# C.net
KiCad netlist of a schematic drawn in Altium Designer
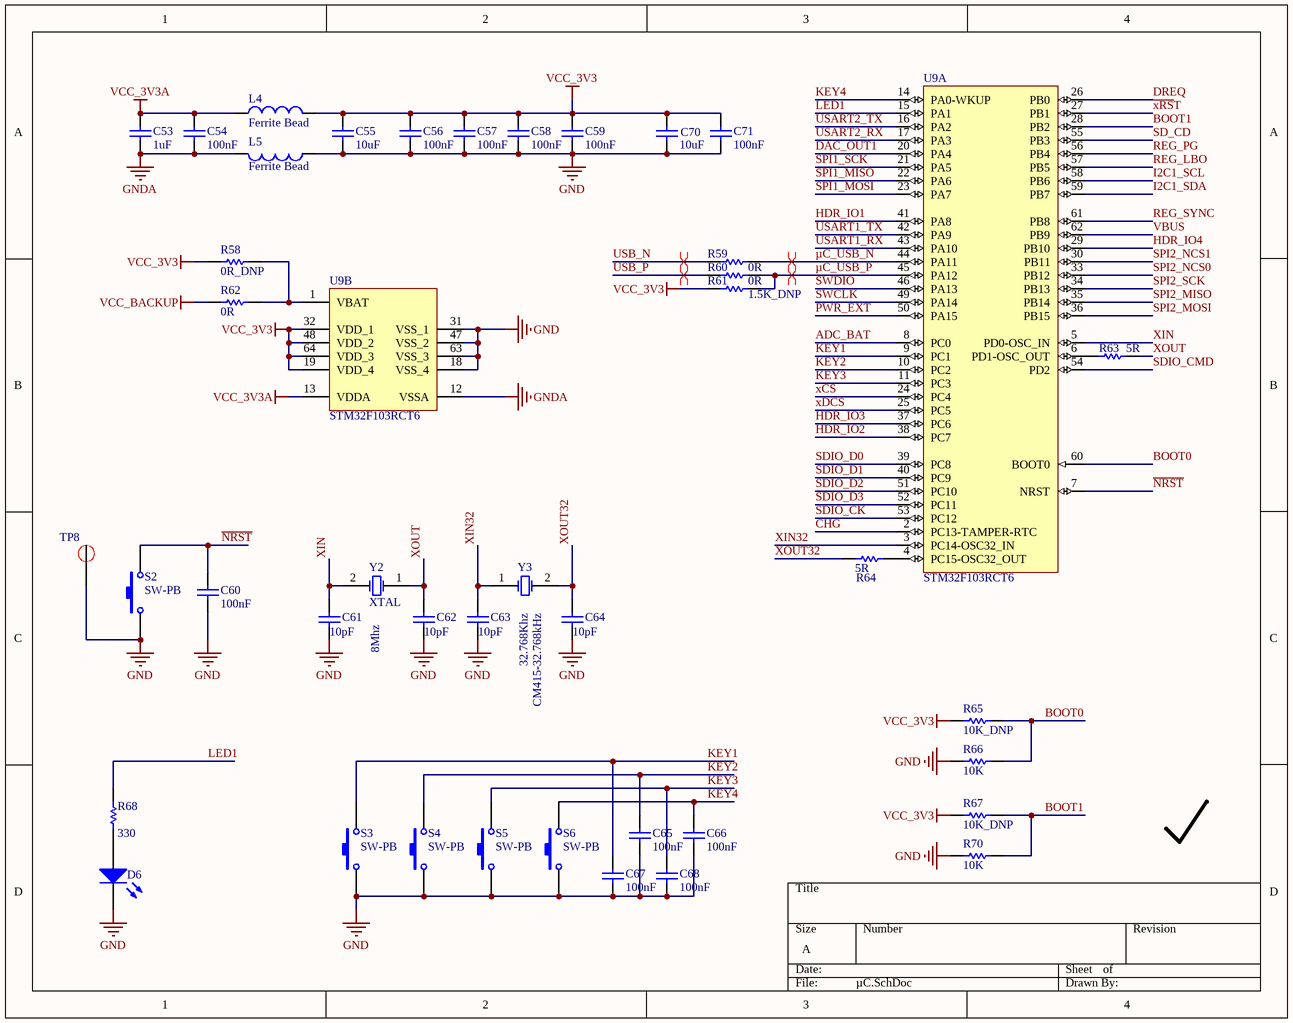
[diagram p0: µC.SchDoc]

(export (version "E")
  (design (tool "Eeschema 10.0.6"))
  (components
    (comp (ref "C53")
      (value "1uF")
      (footprint "0603PKG")
      (description "Capacitor (Semiconductor SIM Model)")
      (fields (field (name "Comment") "Cap Semi") (field (name "PUBLISHER") "Altium Limited"))
      (libsource (lib "Miscellaneous Devices") (part "Cap Semi"))
    )
    (comp (ref "C54")
      (value "100nF")
      (footprint "0603PKG")
      (description "Capacitor (Semiconductor SIM Model)")
      (fields (field (name "Comment") "Cap Semi") (field (name "PUBLISHER") "Altium Limited"))
      (libsource (lib "Miscellaneous Devices") (part "Cap Semi"))
    )
    (comp (ref "C55")
      (value "10uF")
      (footprint "0603PKG")
      (description "Capacitor (Semiconductor SIM Model)")
      (fields (field (name "Comment") "Cap Semi") (field (name "PUBLISHER") "Altium Limited"))
      (libsource (lib "Miscellaneous Devices") (part "Cap Semi"))
    )
    (comp (ref "C56")
      (value "100nF")
      (footprint "0603PKG")
      (description "Capacitor (Semiconductor SIM Model)")
      (fields (field (name "Comment") "Cap Semi") (field (name "PUBLISHER") "Altium Limited"))
      (libsource (lib "Miscellaneous Devices") (part "Cap Semi"))
    )
    (comp (ref "C57")
      (value "100nF")
      (footprint "0603PKG")
      (description "Capacitor (Semiconductor SIM Model)")
      (fields (field (name "Comment") "Cap Semi") (field (name "PUBLISHER") "Altium Limited"))
      (libsource (lib "Miscellaneous Devices") (part "Cap Semi"))
    )
    (comp (ref "C58")
      (value "100nF")
      (footprint "0603PKG")
      (description "Capacitor (Semiconductor SIM Model)")
      (fields (field (name "Comment") "Cap Semi") (field (name "PUBLISHER") "Altium Limited"))
      (libsource (lib "Miscellaneous Devices") (part "Cap Semi"))
    )
    (comp (ref "C59")
      (value "100nF")
      (footprint "0603PKG")
      (description "Capacitor (Semiconductor SIM Model)")
      (fields (field (name "Comment") "Cap Semi") (field (name "PUBLISHER") "Altium Limited"))
      (libsource (lib "Miscellaneous Devices") (part "Cap Semi"))
    )
    (comp (ref "C60")
      (value "100nF")
      (footprint "0603PKG")
      (description "Capacitor (Semiconductor SIM Model)")
      (fields (field (name "Comment") "Cap Semi") (field (name "PUBLISHER") "Altium Limited"))
      (libsource (lib "Miscellaneous Devices") (part "Cap Semi"))
    )
    (comp (ref "C61")
      (value "10pF")
      (footprint "0603PKG")
      (description "Capacitor")
      (fields (field (name "Comment") "Cap") (field (name "PUBLISHER") "Altium Limited"))
      (libsource (lib "Miscellaneous Devices") (part "Cap"))
    )
    (comp (ref "C62")
      (value "10pF")
      (footprint "0603PKG")
      (description "Capacitor")
      (fields (field (name "Comment") "Cap") (field (name "PUBLISHER") "Altium Limited"))
      (libsource (lib "Miscellaneous Devices") (part "Cap"))
    )
    (comp (ref "C63")
      (value "10pF")
      (footprint "0603PKG")
      (description "Capacitor")
      (fields (field (name "Comment") "Cap") (field (name "PUBLISHER") "Altium Limited"))
      (libsource (lib "Miscellaneous Devices") (part "Cap"))
    )
    (comp (ref "C64")
      (value "10pF")
      (footprint "0603PKG")
      (description "Capacitor")
      (fields (field (name "Comment") "Cap") (field (name "PUBLISHER") "Altium Limited"))
      (libsource (lib "Miscellaneous Devices") (part "Cap"))
    )
    (comp (ref "C65")
      (value "100nF")
      (footprint "0603PKG")
      (description "Capacitor (Semiconductor SIM Model)")
      (fields (field (name "Comment") "Cap Semi") (field (name "PUBLISHER") "Altium Limited"))
      (libsource (lib "Miscellaneous Devices") (part "Cap Semi"))
    )
    (comp (ref "C66")
      (value "100nF")
      (footprint "0603PKG")
      (description "Capacitor (Semiconductor SIM Model)")
      (fields (field (name "Comment") "Cap Semi") (field (name "PUBLISHER") "Altium Limited"))
      (libsource (lib "Miscellaneous Devices") (part "Cap Semi"))
    )
    (comp (ref "C67")
      (value "100nF")
      (footprint "0603PKG")
      (description "Capacitor (Semiconductor SIM Model)")
      (fields (field (name "Comment") "Cap Semi") (field (name "PUBLISHER") "Altium Limited"))
      (libsource (lib "Miscellaneous Devices") (part "Cap Semi"))
    )
    (comp (ref "C68")
      (value "100nF")
      (footprint "0603PKG")
      (description "Capacitor (Semiconductor SIM Model)")
      (fields (field (name "Comment") "Cap Semi") (field (name "PUBLISHER") "Altium Limited"))
      (libsource (lib "Miscellaneous Devices") (part "Cap Semi"))
    )
    (comp (ref "C70")
      (value "10uF")
      (footprint "C0805")
      (description "Capacitor (Semiconductor SIM Model)")
      (fields (field (name "Comment") "Cap Semi") (field (name "PUBLISHER") "Altium Limited"))
      (libsource (lib "Miscellaneous Devices") (part "Cap Semi"))
    )
    (comp (ref "C71")
      (value "100nF")
      (footprint "C0805")
      (description "Capacitor (Semiconductor SIM Model)")
      (fields (field (name "Comment") "Cap Semi") (field (name "PUBLISHER") "Altium Limited"))
      (libsource (lib "Miscellaneous Devices") (part "Cap Semi"))
    )
    (comp (ref "D6")
      (value "LED0")
      (footprint "C0805")
      (description "Typical INFRARED GaAs LED")
      (fields (field (name "PUBLISHER") "Altium Limited"))
      (libsource (lib "Miscellaneous Devices") (part "LED0"))
    )
    (comp (ref "L4")
      (value "Ferrite Bead")
      (footprint "C0805")
      (description "Inductor")
      (fields (field (name "PUBLISHER") "Altium Limited"))
      (libsource (lib "Miscellaneous Devices") (part "Inductor"))
    )
    (comp (ref "L5")
      (value "Ferrite Bead")
      (footprint "C0805")
      (description "Inductor")
      (fields (field (name "PUBLISHER") "Altium Limited"))
      (libsource (lib "Miscellaneous Devices") (part "Inductor"))
    )
    (comp (ref "R58")
      (value "0R_DNP")
      (footprint "0603PKG")
      (description "Resistor")
      (fields (field (name "Comment") "Res1") (field (name "PUBLISHER") "Altium Limited"))
      (libsource (lib "Miscellaneous Devices") (part "Res1"))
    )
    (comp (ref "R59")
      (value "0R")
      (footprint "0603PKG")
      (description "Resistor")
      (fields (field (name "Comment") "Res1") (field (name "PUBLISHER") "Altium Limited"))
      (libsource (lib "Miscellaneous Devices") (part "Res1"))
    )
    (comp (ref "R60")
      (value "0R")
      (footprint "0603PKG")
      (description "Resistor")
      (fields (field (name "Comment") "Res1") (field (name "PUBLISHER") "Altium Limited"))
      (libsource (lib "Miscellaneous Devices") (part "Res1"))
    )
    (comp (ref "R61")
      (value "1.5K_DNP")
      (footprint "0603PKG")
      (description "Resistor")
      (fields (field (name "Comment") "Res1") (field (name "PUBLISHER") "Altium Limited"))
      (libsource (lib "Miscellaneous Devices") (part "Res1"))
    )
    (comp (ref "R62")
      (value "0R")
      (footprint "0603PKG")
      (description "Resistor")
      (fields (field (name "Comment") "Res1") (field (name "PUBLISHER") "Altium Limited"))
      (libsource (lib "Miscellaneous Devices") (part "Res1"))
    )
    (comp (ref "R63")
      (value "5R")
      (footprint "0603PKG")
      (description "Resistor")
      (fields (field (name "Comment") "Res1") (field (name "PUBLISHER") "Altium Limited"))
      (libsource (lib "Miscellaneous Devices") (part "Res1"))
    )
    (comp (ref "R64")
      (value "5R")
      (footprint "0603PKG")
      (description "Resistor")
      (fields (field (name "Comment") "Res1") (field (name "PUBLISHER") "Altium Limited"))
      (libsource (lib "Miscellaneous Devices") (part "Res1"))
    )
    (comp (ref "R65")
      (value "10K_DNP")
      (footprint "0603PKG")
      (description "Resistor")
      (fields (field (name "Comment") "Res1") (field (name "PUBLISHER") "Altium Limited"))
      (libsource (lib "Miscellaneous Devices") (part "Res1"))
    )
    (comp (ref "R66")
      (value "10K")
      (footprint "0603PKG")
      (description "Resistor")
      (fields (field (name "Comment") "Res1") (field (name "PUBLISHER") "Altium Limited"))
      (libsource (lib "Miscellaneous Devices") (part "Res1"))
    )
    (comp (ref "R67")
      (value "10K_DNP")
      (footprint "0603PKG")
      (description "Resistor")
      (fields (field (name "Comment") "Res1") (field (name "PUBLISHER") "Altium Limited"))
      (libsource (lib "Miscellaneous Devices") (part "Res1"))
    )
    (comp (ref "R68")
      (value "330")
      (footprint "0603PKG")
      (description "Semiconductor Resistor")
      (fields (field (name "Comment") "Res Semi") (field (name "PUBLISHER") "Altium Limited"))
      (libsource (lib "Miscellaneous Devices") (part "Res Semi"))
    )
    (comp (ref "R70")
      (value "10K")
      (footprint "0603PKG")
      (description "Resistor")
      (fields (field (name "Comment") "Res1") (field (name "PUBLISHER") "Altium Limited"))
      (libsource (lib "Miscellaneous Devices") (part "Res1"))
    )
    (comp (ref "S2")
      (value "SW-PB")
      (footprint "SMD push button")
      (description "Switch")
      (fields (field (name "PUBLISHER") "Altium Limited"))
      (libsource (lib "Miscellaneous Devices") (part "SW-PB"))
    )
    (comp (ref "S3")
      (value "SW-PB")
      (footprint "SMD push button")
      (description "Switch")
      (fields (field (name "PUBLISHER") "Altium Limited"))
      (libsource (lib "Miscellaneous Devices") (part "SW-PB"))
    )
    (comp (ref "S4")
      (value "SW-PB")
      (footprint "SMD push button")
      (description "Switch")
      (fields (field (name "PUBLISHER") "Altium Limited"))
      (libsource (lib "Miscellaneous Devices") (part "SW-PB"))
    )
    (comp (ref "S5")
      (value "SW-PB")
      (footprint "SMD push button")
      (description "Switch")
      (fields (field (name "PUBLISHER") "Altium Limited"))
      (libsource (lib "Miscellaneous Devices") (part "SW-PB"))
    )
    (comp (ref "S6")
      (value "SW-PB")
      (footprint "SMD push button")
      (description "Switch")
      (fields (field (name "PUBLISHER") "Altium Limited"))
      (libsource (lib "Miscellaneous Devices") (part "SW-PB"))
    )
    (comp (ref "TP8")
      (value "TP")
      (footprint "TP_15")
      (libsource (lib "Connector_IntLib") (part "Test Point"))
    )
    (comp (ref "U9")
      (value "STM32F103RCT6")
      (footprint "LQFP64")
      (libsource (lib "STMicroelectronics STM32 F1") (part "STM32F103RCT6"))
    )
    (comp (ref "Y2")
      (value "XTAL")
      (footprint "SMD_Crystal")
      (description "Crystal Oscillator")
      (fields (field (name "ALTIUM_VALUE") "8Mhz") (field (name "PUBLISHER") "Altium Limited"))
      (libsource (lib "Miscellaneous Devices") (part "XTAL"))
    )
    (comp (ref "Y3")
      (value "CM415-32.768kHz")
      (footprint "CM415")
      (description "Crystal Oscillator CM415-32.768kHz")
      (fields (field (name "ALTIUM_VALUE") "32.768Khz") (field (name "PUBLISHER") "Altium Limited"))
      (libsource (lib "Miscellaneous Devices") (part "XTAL"))
    )
  )
  (nets
    (net (code "1") (name "/ADC_BAT") (class "Default")
      (node (ref "U9") (pin "8") (pinfunction "PC0_8") (pintype "bidirectional"))
    )
    (net (code "2") (name "/BOOT0") (class "Default")
      (node (ref "R65") (pin "1") (pinfunction "1_1") (pintype "passive"))
      (node (ref "R66") (pin "1") (pinfunction "1_1") (pintype "passive"))
      (node (ref "U9") (pin "60") (pinfunction "BOOT0_60") (pintype "input"))
    )
    (net (code "3") (name "/BOOT1") (class "Default")
      (node (ref "R67") (pin "1") (pinfunction "1_1") (pintype "passive"))
      (node (ref "R70") (pin "1") (pinfunction "1_1") (pintype "passive"))
      (node (ref "U9") (pin "28") (pinfunction "PB2_28") (pintype "bidirectional"))
    )
    (net (code "4") (name "/DAC_OUT1") (class "Default")
      (node (ref "U9") (pin "20") (pinfunction "PA4_20") (pintype "bidirectional"))
    )
    (net (code "5") (name "/DREQ") (class "Default")
      (node (ref "U9") (pin "26") (pinfunction "PB0_26") (pintype "bidirectional"))
    )
    (net (code "6") (name "/HDR_IO1") (class "Default")
      (node (ref "U9") (pin "41") (pinfunction "PA8_41") (pintype "bidirectional"))
    )
    (net (code "7") (name "/HDR_IO2") (class "Default")
      (node (ref "U9") (pin "38") (pinfunction "PC7_38") (pintype "bidirectional"))
    )
    (net (code "8") (name "/HDR_IO3") (class "Default")
      (node (ref "U9") (pin "37") (pinfunction "PC6_37") (pintype "bidirectional"))
    )
    (net (code "9") (name "/HDR_IO4") (class "Default")
      (node (ref "U9") (pin "29") (pinfunction "PB10_29") (pintype "bidirectional"))
    )
    (net (code "10") (name "/I2C1_SCL") (class "Default")
      (node (ref "U9") (pin "58") (pinfunction "PB6_58") (pintype "bidirectional"))
    )
    (net (code "11") (name "/I2C1_SDA") (class "Default")
      (node (ref "U9") (pin "59") (pinfunction "PB7_59") (pintype "bidirectional"))
    )
    (net (code "12") (name "/KEY1") (class "Default")
      (node (ref "C67") (pin "2") (pinfunction "2_2") (pintype "passive"))
      (node (ref "S3") (pin "2") (pinfunction "2_2") (pintype "passive"))
      (node (ref "U9") (pin "9") (pinfunction "PC1_9") (pintype "bidirectional"))
    )
    (net (code "13") (name "/KEY2") (class "Default")
      (node (ref "C65") (pin "2") (pinfunction "2_2") (pintype "passive"))
      (node (ref "S4") (pin "2") (pinfunction "2_2") (pintype "passive"))
      (node (ref "U9") (pin "10") (pinfunction "PC2_10") (pintype "bidirectional"))
    )
    (net (code "14") (name "/KEY3") (class "Default")
      (node (ref "C68") (pin "2") (pinfunction "2_2") (pintype "passive"))
      (node (ref "S5") (pin "2") (pinfunction "2_2") (pintype "passive"))
      (node (ref "U9") (pin "11") (pinfunction "PC3_11") (pintype "bidirectional"))
    )
    (net (code "15") (name "/KEY4") (class "Default")
      (node (ref "C66") (pin "2") (pinfunction "2_2") (pintype "passive"))
      (node (ref "S6") (pin "2") (pinfunction "2_2") (pintype "passive"))
      (node (ref "U9") (pin "14") (pinfunction "PA0-WKUP_14") (pintype "bidirectional"))
    )
    (net (code "16") (name "/LED1") (class "Default")
      (node (ref "R68") (pin "2") (pinfunction "2_2") (pintype "passive"))
      (node (ref "U9") (pin "15") (pinfunction "PA1_15") (pintype "bidirectional"))
    )
    (net (code "17") (name "/PWR_EXT") (class "Default")
      (node (ref "U9") (pin "50") (pinfunction "PA15_50") (pintype "bidirectional"))
    )
    (net (code "18") (name "/REG_LBO") (class "Default")
      (node (ref "U9") (pin "57") (pinfunction "PB5_57") (pintype "bidirectional"))
    )
    (net (code "19") (name "/REG_PG") (class "Default")
      (node (ref "U9") (pin "56") (pinfunction "PB4_56") (pintype "bidirectional"))
    )
    (net (code "20") (name "/REG_SYNC") (class "Default")
      (node (ref "U9") (pin "61") (pinfunction "PB8_61") (pintype "bidirectional"))
    )
    (net (code "21") (name "/SDIO_CK") (class "Default")
      (node (ref "U9") (pin "53") (pinfunction "PC12_53") (pintype "bidirectional"))
    )
    (net (code "22") (name "/SDIO_CMD") (class "Default")
      (node (ref "U9") (pin "54") (pinfunction "PD2_54") (pintype "bidirectional"))
    )
    (net (code "23") (name "/SDIO_D0") (class "Default")
      (node (ref "U9") (pin "39") (pinfunction "PC8_39") (pintype "bidirectional"))
    )
    (net (code "24") (name "/SDIO_D1") (class "Default")
      (node (ref "U9") (pin "40") (pinfunction "PC9_40") (pintype "bidirectional"))
    )
    (net (code "25") (name "/SDIO_D2") (class "Default")
      (node (ref "U9") (pin "51") (pinfunction "PC10_51") (pintype "bidirectional"))
    )
    (net (code "26") (name "/SDIO_D3") (class "Default")
      (node (ref "U9") (pin "52") (pinfunction "PC11_52") (pintype "bidirectional"))
    )
    (net (code "27") (name "/SD_CD") (class "Default")
      (node (ref "U9") (pin "55") (pinfunction "PB3_55") (pintype "bidirectional"))
    )
    (net (code "28") (name "/SPI1_MISO") (class "Default")
      (node (ref "U9") (pin "22") (pinfunction "PA6_22") (pintype "bidirectional"))
    )
    (net (code "29") (name "/SPI1_MOSI") (class "Default")
      (node (ref "U9") (pin "23") (pinfunction "PA7_23") (pintype "bidirectional"))
    )
    (net (code "30") (name "/SPI1_SCK") (class "Default")
      (node (ref "U9") (pin "21") (pinfunction "PA5_21") (pintype "bidirectional"))
    )
    (net (code "31") (name "/SPI2_MISO") (class "Default")
      (node (ref "U9") (pin "35") (pinfunction "PB14_35") (pintype "bidirectional"))
    )
    (net (code "32") (name "/SPI2_MOSI") (class "Default")
      (node (ref "U9") (pin "36") (pinfunction "PB15_36") (pintype "bidirectional"))
    )
    (net (code "33") (name "/SPI2_NCS0") (class "Default")
      (node (ref "U9") (pin "33") (pinfunction "PB12_33") (pintype "bidirectional"))
    )
    (net (code "34") (name "/SPI2_NCS1") (class "Default")
      (node (ref "U9") (pin "30") (pinfunction "PB11_30") (pintype "bidirectional"))
    )
    (net (code "35") (name "/SPI2_SCK") (class "Default")
      (node (ref "U9") (pin "34") (pinfunction "PB13_34") (pintype "bidirectional"))
    )
    (net (code "36") (name "/SWCLK") (class "Default")
      (node (ref "U9") (pin "49") (pinfunction "PA14_49") (pintype "bidirectional"))
    )
    (net (code "37") (name "/SWDIO") (class "Default")
      (node (ref "U9") (pin "46") (pinfunction "PA13_46") (pintype "bidirectional"))
    )
    (net (code "38") (name "/USART1_RX") (class "Default")
      (node (ref "U9") (pin "43") (pinfunction "PA10_43") (pintype "bidirectional"))
    )
    (net (code "39") (name "/USART1_TX") (class "Default")
      (node (ref "U9") (pin "42") (pinfunction "PA9_42") (pintype "bidirectional"))
    )
    (net (code "40") (name "/USART2_RX") (class "Default")
      (node (ref "U9") (pin "17") (pinfunction "PA3_17") (pintype "bidirectional"))
    )
    (net (code "41") (name "/USART2_TX") (class "Default")
      (node (ref "U9") (pin "16") (pinfunction "PA2_16") (pintype "bidirectional"))
    )
    (net (code "42") (name "/USB_N") (class "Default")
      (node (ref "R59") (pin "2") (pinfunction "2_2") (pintype "passive"))
    )
    (net (code "43") (name "/USB_P") (class "Default")
      (node (ref "R60") (pin "2") (pinfunction "2_2") (pintype "passive"))
    )
    (net (code "44") (name "/VBUS") (class "Default")
      (node (ref "U9") (pin "62") (pinfunction "PB9_62") (pintype "bidirectional"))
    )
    (net (code "45") (name "/XIN") (class "Default")
      (node (ref "C61") (pin "2") (pinfunction "2_2") (pintype "passive"))
      (node (ref "U9") (pin "5") (pinfunction "PD0-OSC_IN_5") (pintype "bidirectional"))
      (node (ref "Y2") (pin "2") (pinfunction "OSC2_2") (pintype "passive"))
    )
    (net (code "46") (name "/XIN32") (class "Default")
      (node (ref "C63") (pin "2") (pinfunction "2_2") (pintype "passive"))
      (node (ref "U9") (pin "3") (pinfunction "PC14-OSC32_IN_3") (pintype "bidirectional"))
      (node (ref "Y3") (pin "1") (pinfunction "OSC1_1") (pintype "passive"))
    )
    (net (code "47") (name "/XOUT") (class "Default")
      (node (ref "C62") (pin "2") (pinfunction "2_2") (pintype "passive"))
      (node (ref "R63") (pin "1") (pinfunction "1_1") (pintype "passive"))
      (node (ref "Y2") (pin "1") (pinfunction "OSC1_1") (pintype "passive"))
    )
    (net (code "48") (name "/XOUT32") (class "Default")
      (node (ref "C64") (pin "2") (pinfunction "2_2") (pintype "passive"))
      (node (ref "R64") (pin "2") (pinfunction "2_2") (pintype "passive"))
      (node (ref "Y3") (pin "2") (pinfunction "OSC2_2") (pintype "passive"))
    )
    (net (code "49") (name "/~{CHG}") (class "Default")
      (node (ref "U9") (pin "2") (pinfunction "PC13-TAMPER-RTC_2") (pintype "bidirectional"))
    )
    (net (code "50") (name "/~{NRST}") (class "Default")
      (node (ref "C60") (pin "2") (pinfunction "2_2") (pintype "passive"))
      (node (ref "S2") (pin "2") (pinfunction "2_2") (pintype "passive"))
      (node (ref "U9") (pin "7") (pinfunction "NRST_7") (pintype "bidirectional"))
    )
    (net (code "51") (name "/~{xCS}") (class "Default")
      (node (ref "U9") (pin "24") (pinfunction "PC4_24") (pintype "bidirectional"))
    )
    (net (code "52") (name "/~{xDCS}") (class "Default")
      (node (ref "U9") (pin "25") (pinfunction "PC5_25") (pintype "bidirectional"))
    )
    (net (code "53") (name "/~{xRS}T") (class "Default")
      (node (ref "U9") (pin "27") (pinfunction "PB1_27") (pintype "bidirectional"))
    )
    (net (code "54") (name "/µC_USB_N") (class "Default")
      (node (ref "R59") (pin "1") (pinfunction "1_1") (pintype "passive"))
      (node (ref "U9") (pin "44") (pinfunction "PA11_44") (pintype "bidirectional"))
    )
    (net (code "55") (name "/µC_USB_P") (class "Default")
      (node (ref "R60") (pin "1") (pinfunction "1_1") (pintype "passive"))
      (node (ref "R61") (pin "1") (pinfunction "1_1") (pintype "passive"))
      (node (ref "U9") (pin "45") (pinfunction "PA12_45") (pintype "bidirectional"))
    )
    (net (code "56") (name "GND") (class "Default")
      (node (ref "C55") (pin "1") (pinfunction "1_1") (pintype "passive"))
      (node (ref "C56") (pin "1") (pinfunction "1_1") (pintype "passive"))
      (node (ref "C57") (pin "1") (pinfunction "1_1") (pintype "passive"))
      (node (ref "C58") (pin "1") (pinfunction "1_1") (pintype "passive"))
      (node (ref "C59") (pin "1") (pinfunction "1_1") (pintype "passive"))
      (node (ref "C60") (pin "1") (pinfunction "1_1") (pintype "passive"))
      (node (ref "C61") (pin "1") (pinfunction "1_1") (pintype "passive"))
      (node (ref "C62") (pin "1") (pinfunction "1_1") (pintype "passive"))
      (node (ref "C63") (pin "1") (pinfunction "1_1") (pintype "passive"))
      (node (ref "C64") (pin "1") (pinfunction "1_1") (pintype "passive"))
      (node (ref "C65") (pin "1") (pinfunction "1_1") (pintype "passive"))
      (node (ref "C66") (pin "1") (pinfunction "1_1") (pintype "passive"))
      (node (ref "C67") (pin "1") (pinfunction "1_1") (pintype "passive"))
      (node (ref "C68") (pin "1") (pinfunction "1_1") (pintype "passive"))
      (node (ref "C70") (pin "1") (pinfunction "1_1") (pintype "passive"))
      (node (ref "C71") (pin "1") (pinfunction "1_1") (pintype "passive"))
      (node (ref "D6") (pin "2") (pinfunction "K_2") (pintype "passive"))
      (node (ref "L5") (pin "1") (pinfunction "1_1") (pintype "passive"))
      (node (ref "R66") (pin "2") (pinfunction "2_2") (pintype "passive"))
      (node (ref "R70") (pin "2") (pinfunction "2_2") (pintype "passive"))
      (node (ref "S2") (pin "1") (pinfunction "1_1") (pintype "passive"))
      (node (ref "S3") (pin "1") (pinfunction "1_1") (pintype "passive"))
      (node (ref "S4") (pin "1") (pinfunction "1_1") (pintype "passive"))
      (node (ref "S5") (pin "1") (pinfunction "1_1") (pintype "passive"))
      (node (ref "S6") (pin "1") (pinfunction "1_1") (pintype "passive"))
      (node (ref "TP8") (pin "1") (pinfunction "1_1") (pintype "passive"))
      (node (ref "U9") (pin "18") (pinfunction "VSS_4_18") (pintype "power_in"))
      (node (ref "U9") (pin "31") (pinfunction "VSS_1_31") (pintype "power_in"))
      (node (ref "U9") (pin "47") (pinfunction "VSS_2_47") (pintype "power_in"))
      (node (ref "U9") (pin "63") (pinfunction "VSS_3_63") (pintype "power_in"))
    )
    (net (code "57") (name "GNDA") (class "Default")
      (node (ref "C53") (pin "1") (pinfunction "1_1") (pintype "passive"))
      (node (ref "C54") (pin "1") (pinfunction "1_1") (pintype "passive"))
      (node (ref "L5") (pin "2") (pinfunction "2_2") (pintype "passive"))
      (node (ref "U9") (pin "12") (pinfunction "VSSA_12") (pintype "power_in"))
    )
    (net (code "58") (name "Net-(D6-A)") (class "Default")
      (node (ref "D6") (pin "1") (pinfunction "A_1") (pintype "passive"))
      (node (ref "R68") (pin "1") (pinfunction "1_1") (pintype "passive"))
    )
    (net (code "59") (name "Net-(U9A-PC15-OSC32_OUT)") (class "Default")
      (node (ref "R64") (pin "1") (pinfunction "1_1") (pintype "passive"))
      (node (ref "U9") (pin "4") (pinfunction "PC15-OSC32_OUT_4") (pintype "bidirectional"))
    )
    (net (code "60") (name "Net-(U9A-PD1-OSC_OUT)") (class "Default")
      (node (ref "R63") (pin "2") (pinfunction "2_2") (pintype "passive"))
      (node (ref "U9") (pin "6") (pinfunction "PD1-OSC_OUT_6") (pintype "bidirectional"))
    )
    (net (code "61") (name "Net-(U9B-VBAT)") (class "Default")
      (node (ref "R58") (pin "1") (pinfunction "1_1") (pintype "passive"))
      (node (ref "R62") (pin "1") (pinfunction "1_1") (pintype "passive"))
      (node (ref "U9") (pin "1") (pinfunction "VBAT_1") (pintype "power_in"))
    )
    (net (code "62") (name "VCC_3V3") (class "Default")
      (node (ref "C55") (pin "2") (pinfunction "2_2") (pintype "passive"))
      (node (ref "C56") (pin "2") (pinfunction "2_2") (pintype "passive"))
      (node (ref "C57") (pin "2") (pinfunction "2_2") (pintype "passive"))
      (node (ref "C58") (pin "2") (pinfunction "2_2") (pintype "passive"))
      (node (ref "C59") (pin "2") (pinfunction "2_2") (pintype "passive"))
      (node (ref "C70") (pin "2") (pinfunction "2_2") (pintype "passive"))
      (node (ref "C71") (pin "2") (pinfunction "2_2") (pintype "passive"))
      (node (ref "L4") (pin "2") (pinfunction "2_2") (pintype "passive"))
      (node (ref "R58") (pin "2") (pinfunction "2_2") (pintype "passive"))
      (node (ref "R61") (pin "2") (pinfunction "2_2") (pintype "passive"))
      (node (ref "R65") (pin "2") (pinfunction "2_2") (pintype "passive"))
      (node (ref "R67") (pin "2") (pinfunction "2_2") (pintype "passive"))
      (node (ref "U9") (pin "19") (pinfunction "VDD_4_19") (pintype "power_in"))
      (node (ref "U9") (pin "32") (pinfunction "VDD_1_32") (pintype "power_in"))
      (node (ref "U9") (pin "48") (pinfunction "VDD_2_48") (pintype "power_in"))
      (node (ref "U9") (pin "64") (pinfunction "VDD_3_64") (pintype "power_in"))
    )
    (net (code "63") (name "VCC_3V3A") (class "Default")
      (node (ref "C53") (pin "2") (pinfunction "2_2") (pintype "passive"))
      (node (ref "C54") (pin "2") (pinfunction "2_2") (pintype "passive"))
      (node (ref "L4") (pin "1") (pinfunction "1_1") (pintype "passive"))
      (node (ref "U9") (pin "13") (pinfunction "VDDA_13") (pintype "power_in"))
    )
    (net (code "64") (name "VCC_BACKUP") (class "Default")
      (node (ref "R62") (pin "2") (pinfunction "2_2") (pintype "passive"))
    )
  )
)
